# power.net
KiCad netlist of a schematic drawn in Altium Designer
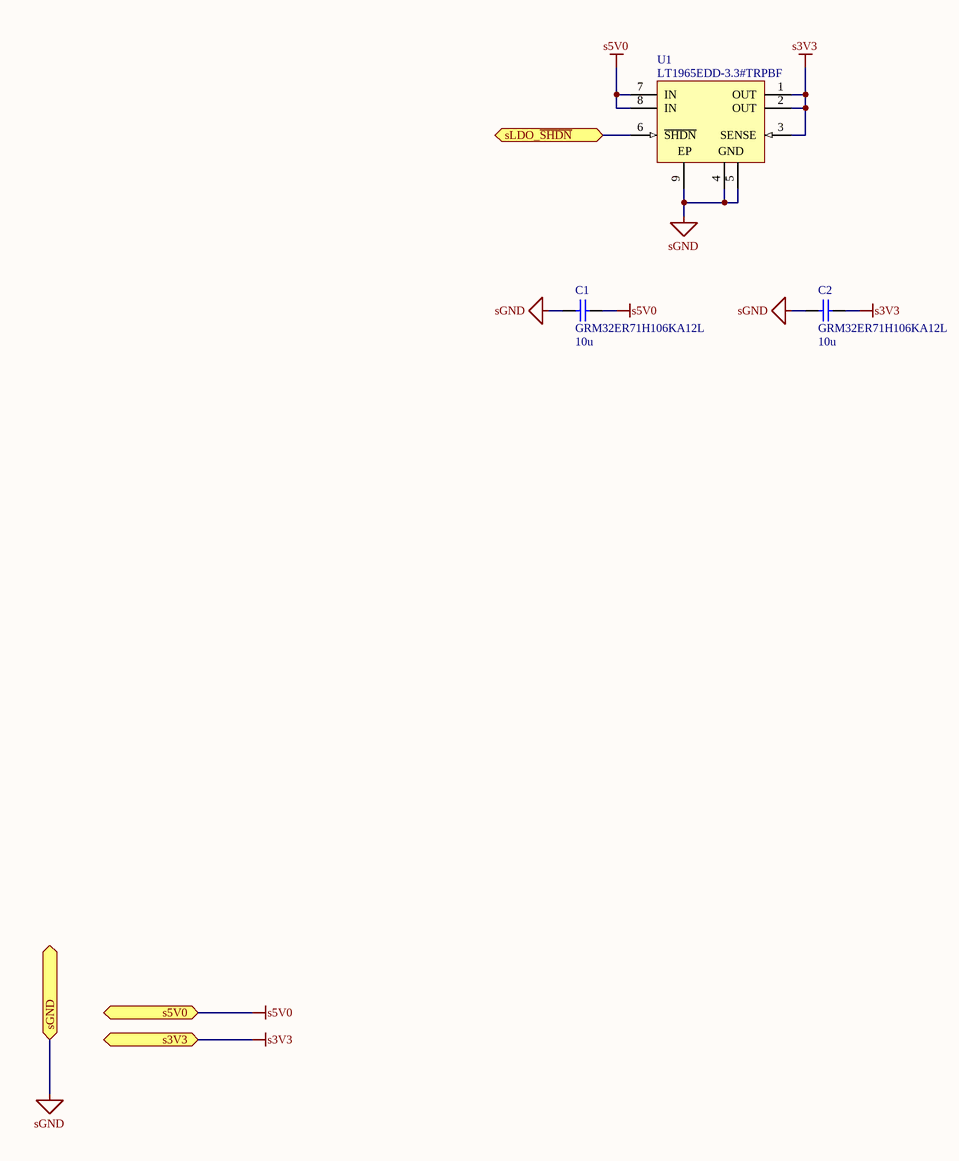
[diagram p0: power.SchDoc]

(export (version "E")
  (design (tool "Eeschema 10.0.6"))
  (components
    (comp (ref "C1")
      (value "GRM32ER71H106KA12L")
      (footprint "1210")
      (description "-55-125C, 1005, 50V, X7R, ±10%")
      (fields (field (name "ALTIUM_VALUE") "10u"))
      (libsource (lib "standard_capacitors") (part "GRM32ER71HxxxKdddd"))
    )
    (comp (ref "C2")
      (value "GRM32ER71H106KA12L")
      (footprint "1210")
      (description "-55-125C, 1005, 50V, X7R, ±10%")
      (fields (field (name "ALTIUM_VALUE") "10u"))
      (libsource (lib "standard_capacitors") (part "GRM32ER71HxxxKdddd"))
    )
    (comp (ref "U1")
      (value "LT1965EDD-3.3#TRPBF")
      (footprint "LT-DD-8_V")
      (fields (field (name "MANUFACTURER") "Linear Technology"))
      (libsource (lib "Altium Content Vault") (part "CMP-0476-00225-1"))
    )
  )
  (nets
    (net (code "1") (name "/sLDO_~{SHDN}") (class "Default")
      (node (ref "U1") (pin "6") (pinfunction "~{SHDN}_6") (pintype "input"))
    )
    (net (code "2") (name "s3V3") (class "Default")
      (node (ref "C2") (pin "2") (pinfunction "2_2") (pintype "passive"))
      (node (ref "U1") (pin "1") (pinfunction "OUT_1") (pintype "power_in"))
      (node (ref "U1") (pin "2") (pinfunction "OUT_2") (pintype "power_in"))
      (node (ref "U1") (pin "3") (pinfunction "SENSE_3") (pintype "input"))
    )
    (net (code "3") (name "s5V0") (class "Default")
      (node (ref "C1") (pin "2") (pinfunction "2_2") (pintype "passive"))
      (node (ref "U1") (pin "7") (pinfunction "IN_7") (pintype "power_in"))
      (node (ref "U1") (pin "8") (pinfunction "IN_8") (pintype "power_in"))
    )
    (net (code "4") (name "sGND") (class "Default")
      (node (ref "C1") (pin "1") (pinfunction "1_1") (pintype "passive"))
      (node (ref "C2") (pin "1") (pinfunction "1_1") (pintype "passive"))
      (node (ref "U1") (pin "4") (pinfunction "GND_4") (pintype "power_in"))
      (node (ref "U1") (pin "5") (pinfunction "GND_5") (pintype "power_in"))
      (node (ref "U1") (pin "9") (pinfunction "EP_9") (pintype "power_in"))
    )
  )
)
